# tricorder-photodiode-breakout-mk-1_2.net
KiCad netlist of a schematic drawn in EAGLE
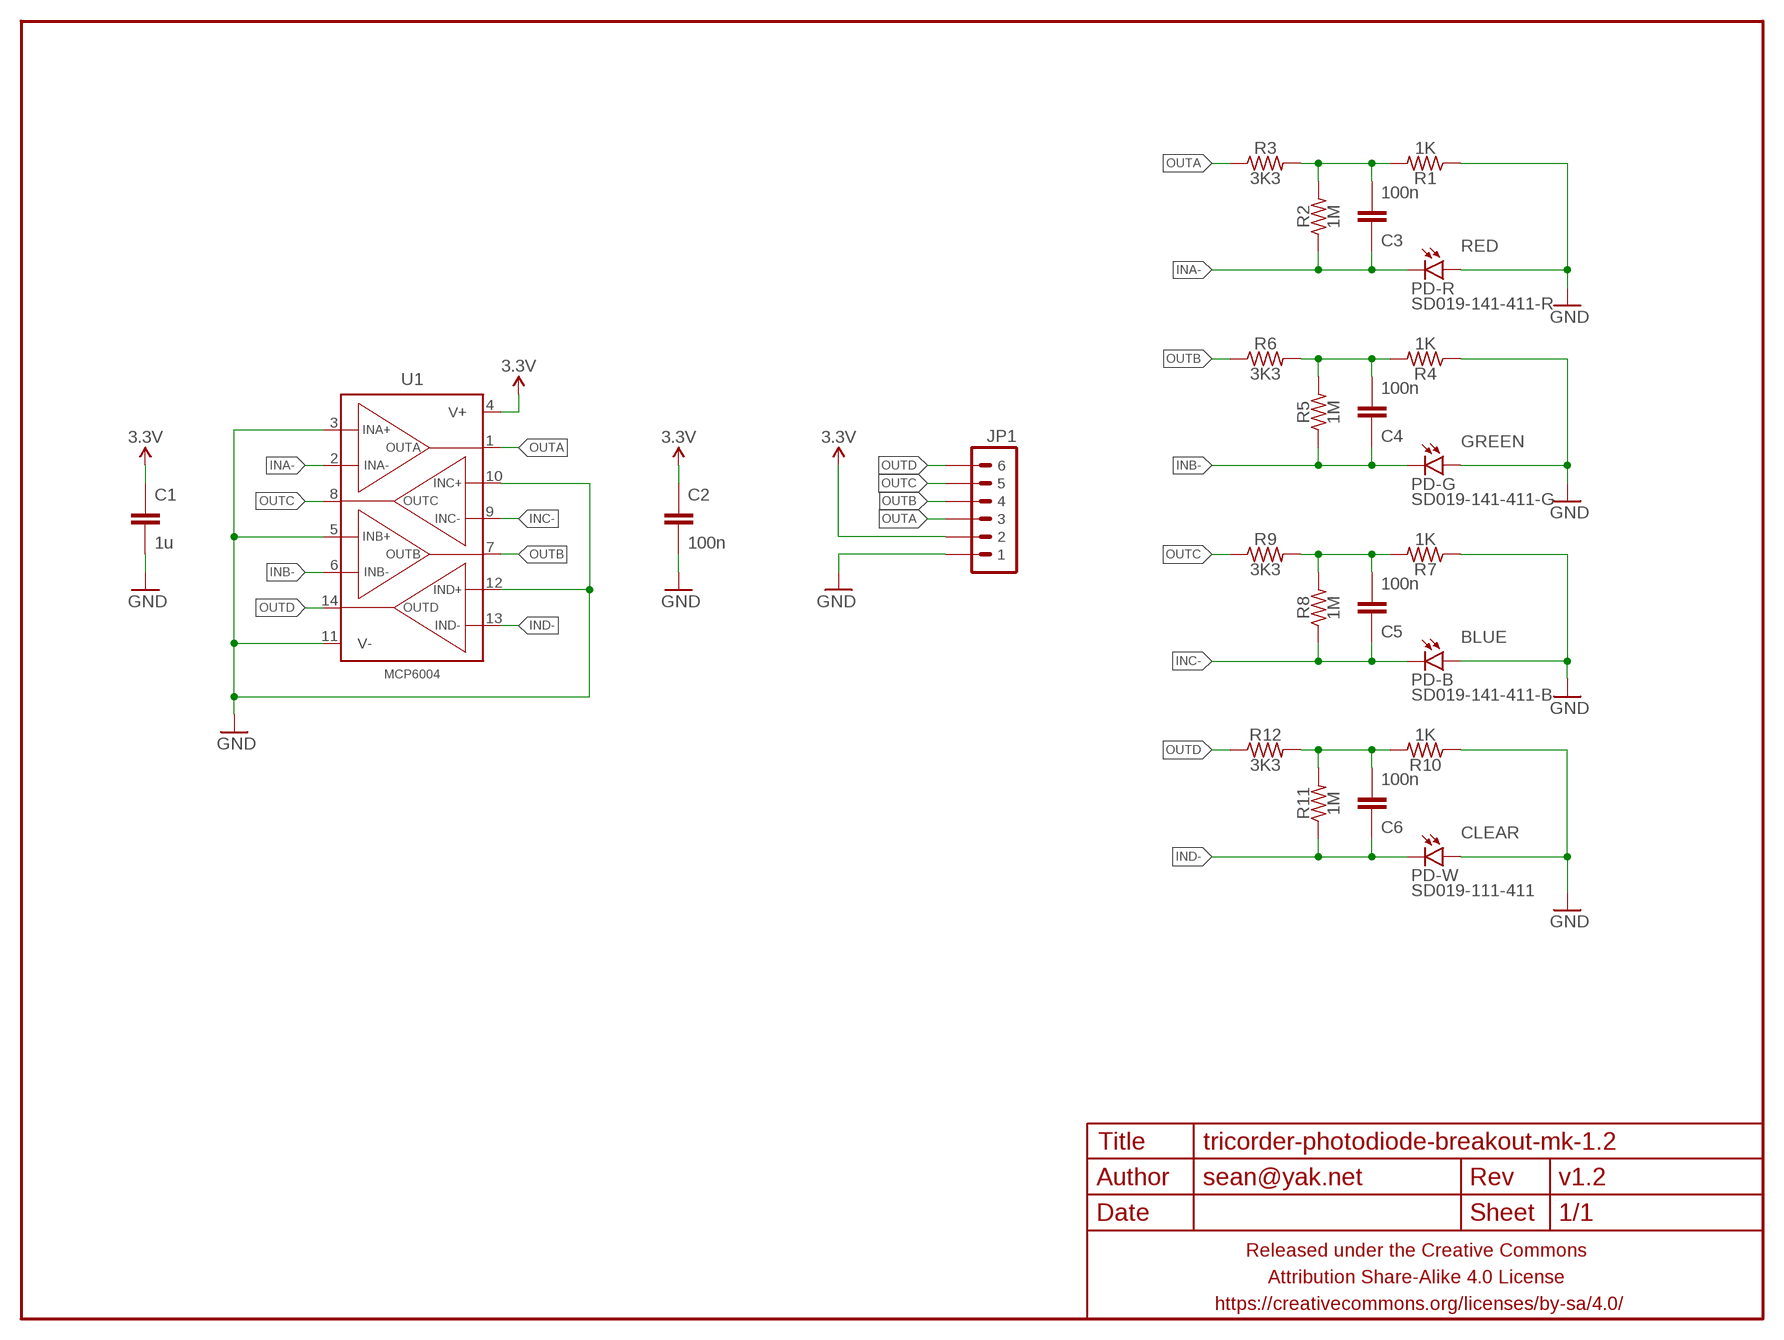
[diagram p0: schematic, sheet 1]

(export (version "E")
  (design (tool "Eeschema 10.0.6"))
  (components
    (comp (ref "C1")
      (value "1u")
      (footprint "eagle-import:C0603")
      (libsource (lib "eagle-import") (part "CAPACITOR-CERAMICC0603"))
    )
    (comp (ref "C2")
      (value "100n")
      (footprint "eagle-import:C0603")
      (libsource (lib "eagle-import") (part "CAPACITOR-CERAMICC0603"))
    )
    (comp (ref "C3")
      (value "100n")
      (footprint "eagle-import:C0603")
      (libsource (lib "eagle-import") (part "CAPACITOR-CERAMICC0603"))
    )
    (comp (ref "C4")
      (value "100n")
      (footprint "eagle-import:C0603")
      (libsource (lib "eagle-import") (part "CAPACITOR-CERAMICC0603"))
    )
    (comp (ref "C5")
      (value "100n")
      (footprint "eagle-import:C0603")
      (libsource (lib "eagle-import") (part "CAPACITOR-CERAMICC0603"))
    )
    (comp (ref "C6")
      (value "100n")
      (footprint "eagle-import:C0603")
      (libsource (lib "eagle-import") (part "CAPACITOR-CERAMICC0603"))
    )
    (comp (ref "FRAME1")
      (value "FRAME-LETTERNO_PACKAGE")
      (footprint "eagle-import:DUMMY")
      (fields (field (name "DESIGNER") "sean@yak.net") (field (name "VERSION") "v1.2"))
      (libsource (lib "eagle-import") (part "FRAME-LETTERNO_PACKAGE"))
    )
    (comp (ref "JP1")
      (value "M06PTH_CENTERED")
      (footprint "eagle-import:1X06_CENTERED")
      (libsource (lib "eagle-import") (part "M06PTH_CENTERED"))
    )
    (comp (ref "PD-B")
      (value "SD019-141-411-B")
      (footprint "eagle-import:LED-0805")
      (libsource (lib "eagle-import") (part "PHOTODIODESMD-0805"))
    )
    (comp (ref "PD-G")
      (value "SD019-141-411-G")
      (footprint "eagle-import:LED-0805")
      (libsource (lib "eagle-import") (part "PHOTODIODESMD-0805"))
    )
    (comp (ref "PD-R")
      (value "SD019-141-411-R")
      (footprint "eagle-import:LED-0805")
      (libsource (lib "eagle-import") (part "PHOTODIODESMD-0805"))
    )
    (comp (ref "PD-W")
      (value "SD019-111-411")
      (footprint "eagle-import:LED-0805")
      (libsource (lib "eagle-import") (part "PHOTODIODESMD-0805"))
    )
    (comp (ref "R1")
      (value "1K")
      (footprint "eagle-import:R0603")
      (libsource (lib "eagle-import") (part "RESISTORR0603"))
    )
    (comp (ref "R2")
      (value "1M")
      (footprint "eagle-import:R0603")
      (libsource (lib "eagle-import") (part "RESISTORR0603"))
    )
    (comp (ref "R3")
      (value "3K3")
      (footprint "eagle-import:R0603")
      (libsource (lib "eagle-import") (part "RESISTORR0603"))
    )
    (comp (ref "R4")
      (value "1K")
      (footprint "eagle-import:R0603")
      (libsource (lib "eagle-import") (part "RESISTORR0603"))
    )
    (comp (ref "R5")
      (value "1M")
      (footprint "eagle-import:R0603")
      (libsource (lib "eagle-import") (part "RESISTORR0603"))
    )
    (comp (ref "R6")
      (value "3K3")
      (footprint "eagle-import:R0603")
      (libsource (lib "eagle-import") (part "RESISTORR0603"))
    )
    (comp (ref "R7")
      (value "1K")
      (footprint "eagle-import:R0603")
      (libsource (lib "eagle-import") (part "RESISTORR0603"))
    )
    (comp (ref "R8")
      (value "1M")
      (footprint "eagle-import:R0603")
      (libsource (lib "eagle-import") (part "RESISTORR0603"))
    )
    (comp (ref "R9")
      (value "3K3")
      (footprint "eagle-import:R0603")
      (libsource (lib "eagle-import") (part "RESISTORR0603"))
    )
    (comp (ref "R10")
      (value "1K")
      (footprint "eagle-import:R0603")
      (libsource (lib "eagle-import") (part "RESISTORR0603"))
    )
    (comp (ref "R11")
      (value "1M")
      (footprint "eagle-import:R0603")
      (libsource (lib "eagle-import") (part "RESISTORR0603"))
    )
    (comp (ref "R12")
      (value "3K3")
      (footprint "eagle-import:R0603")
      (libsource (lib "eagle-import") (part "RESISTORR0603"))
    )
    (comp (ref "U1")
      (value "MCP6004")
      (footprint "eagle-import:SO14")
      (libsource (lib "eagle-import") (part "MCP6004SOIC14"))
    )
  )
  (nets
    (net (code "1") (name "3.3V") (class "Default")
      (node (ref "C1") (pin "1") (pinfunction "1_1") (pintype "passive"))
      (node (ref "C2") (pin "1") (pinfunction "1_1") (pintype "passive"))
      (node (ref "JP1") (pin "2") (pinfunction "2_2") (pintype "passive"))
      (node (ref "U1") (pin "4") (pinfunction "V+_4") (pintype "power_in"))
    )
    (net (code "2") (name "GND") (class "Default")
      (node (ref "C1") (pin "2") (pinfunction "2_2") (pintype "passive"))
      (node (ref "C2") (pin "2") (pinfunction "2_2") (pintype "passive"))
      (node (ref "JP1") (pin "1") (pinfunction "1_1") (pintype "passive"))
      (node (ref "PD-B") (pin "A") (pinfunction "A_A") (pintype "passive"))
      (node (ref "PD-G") (pin "A") (pinfunction "A_A") (pintype "passive"))
      (node (ref "PD-R") (pin "A") (pinfunction "A_A") (pintype "passive"))
      (node (ref "PD-W") (pin "A") (pinfunction "A_A") (pintype "passive"))
      (node (ref "R1") (pin "1") (pinfunction "1_1") (pintype "passive"))
      (node (ref "R10") (pin "1") (pinfunction "1_1") (pintype "passive"))
      (node (ref "R4") (pin "1") (pinfunction "1_1") (pintype "passive"))
      (node (ref "R7") (pin "1") (pinfunction "1_1") (pintype "passive"))
      (node (ref "U1") (pin "10") (pinfunction "INC+_10") (pintype "input"))
      (node (ref "U1") (pin "11") (pinfunction "V-_11") (pintype "power_in"))
      (node (ref "U1") (pin "12") (pinfunction "IND+_12") (pintype "input"))
      (node (ref "U1") (pin "3") (pinfunction "INA+_3") (pintype "input"))
      (node (ref "U1") (pin "5") (pinfunction "INB+_5") (pintype "input"))
    )
    (net (code "3") (name "INA-") (class "Default")
      (node (ref "C3") (pin "1") (pinfunction "1_1") (pintype "passive"))
      (node (ref "PD-R") (pin "C") (pinfunction "C_C") (pintype "passive"))
      (node (ref "R2") (pin "1") (pinfunction "1_1") (pintype "passive"))
      (node (ref "U1") (pin "2") (pinfunction "INA-_2") (pintype "input"))
    )
    (net (code "4") (name "INB-") (class "Default")
      (node (ref "C4") (pin "1") (pinfunction "1_1") (pintype "passive"))
      (node (ref "PD-G") (pin "C") (pinfunction "C_C") (pintype "passive"))
      (node (ref "R5") (pin "1") (pinfunction "1_1") (pintype "passive"))
      (node (ref "U1") (pin "6") (pinfunction "INB-_6") (pintype "input"))
    )
    (net (code "5") (name "INC-") (class "Default")
      (node (ref "C5") (pin "1") (pinfunction "1_1") (pintype "passive"))
      (node (ref "PD-B") (pin "C") (pinfunction "C_C") (pintype "passive"))
      (node (ref "R8") (pin "1") (pinfunction "1_1") (pintype "passive"))
      (node (ref "U1") (pin "9") (pinfunction "INC-_9") (pintype "input"))
    )
    (net (code "6") (name "IND-") (class "Default")
      (node (ref "C6") (pin "1") (pinfunction "1_1") (pintype "passive"))
      (node (ref "PD-W") (pin "C") (pinfunction "C_C") (pintype "passive"))
      (node (ref "R11") (pin "1") (pinfunction "1_1") (pintype "passive"))
      (node (ref "U1") (pin "13") (pinfunction "IND-_13") (pintype "input"))
    )
    (net (code "7") (name "Net-(C3-Pad2)") (class "Default")
      (node (ref "C3") (pin "2") (pinfunction "2_2") (pintype "passive"))
      (node (ref "R1") (pin "2") (pinfunction "2_2") (pintype "passive"))
      (node (ref "R2") (pin "2") (pinfunction "2_2") (pintype "passive"))
      (node (ref "R3") (pin "2") (pinfunction "2_2") (pintype "passive"))
    )
    (net (code "8") (name "Net-(C4-Pad2)") (class "Default")
      (node (ref "C4") (pin "2") (pinfunction "2_2") (pintype "passive"))
      (node (ref "R4") (pin "2") (pinfunction "2_2") (pintype "passive"))
      (node (ref "R5") (pin "2") (pinfunction "2_2") (pintype "passive"))
      (node (ref "R6") (pin "2") (pinfunction "2_2") (pintype "passive"))
    )
    (net (code "9") (name "Net-(C5-Pad2)") (class "Default")
      (node (ref "C5") (pin "2") (pinfunction "2_2") (pintype "passive"))
      (node (ref "R7") (pin "2") (pinfunction "2_2") (pintype "passive"))
      (node (ref "R8") (pin "2") (pinfunction "2_2") (pintype "passive"))
      (node (ref "R9") (pin "2") (pinfunction "2_2") (pintype "passive"))
    )
    (net (code "10") (name "Net-(C6-Pad2)") (class "Default")
      (node (ref "C6") (pin "2") (pinfunction "2_2") (pintype "passive"))
      (node (ref "R10") (pin "2") (pinfunction "2_2") (pintype "passive"))
      (node (ref "R11") (pin "2") (pinfunction "2_2") (pintype "passive"))
      (node (ref "R12") (pin "2") (pinfunction "2_2") (pintype "passive"))
    )
    (net (code "11") (name "OUTA") (class "Default")
      (node (ref "JP1") (pin "3") (pinfunction "3_3") (pintype "passive"))
      (node (ref "R3") (pin "1") (pinfunction "1_1") (pintype "passive"))
      (node (ref "U1") (pin "1") (pinfunction "OUTA_1") (pintype "output"))
    )
    (net (code "12") (name "OUTB") (class "Default")
      (node (ref "JP1") (pin "4") (pinfunction "4_4") (pintype "passive"))
      (node (ref "R6") (pin "1") (pinfunction "1_1") (pintype "passive"))
      (node (ref "U1") (pin "7") (pinfunction "OUTB_7") (pintype "output"))
    )
    (net (code "13") (name "OUTC") (class "Default")
      (node (ref "JP1") (pin "5") (pinfunction "5_5") (pintype "passive"))
      (node (ref "R9") (pin "1") (pinfunction "1_1") (pintype "passive"))
      (node (ref "U1") (pin "8") (pinfunction "OUTC_8") (pintype "output"))
    )
    (net (code "14") (name "OUTD") (class "Default")
      (node (ref "JP1") (pin "6") (pinfunction "6_6") (pintype "passive"))
      (node (ref "R12") (pin "1") (pinfunction "1_1") (pintype "passive"))
      (node (ref "U1") (pin "14") (pinfunction "OUTD_14") (pintype "output"))
    )
  )
)
